# Fan_Feedback.net
KiCad netlist of a schematic drawn in Altium Designer
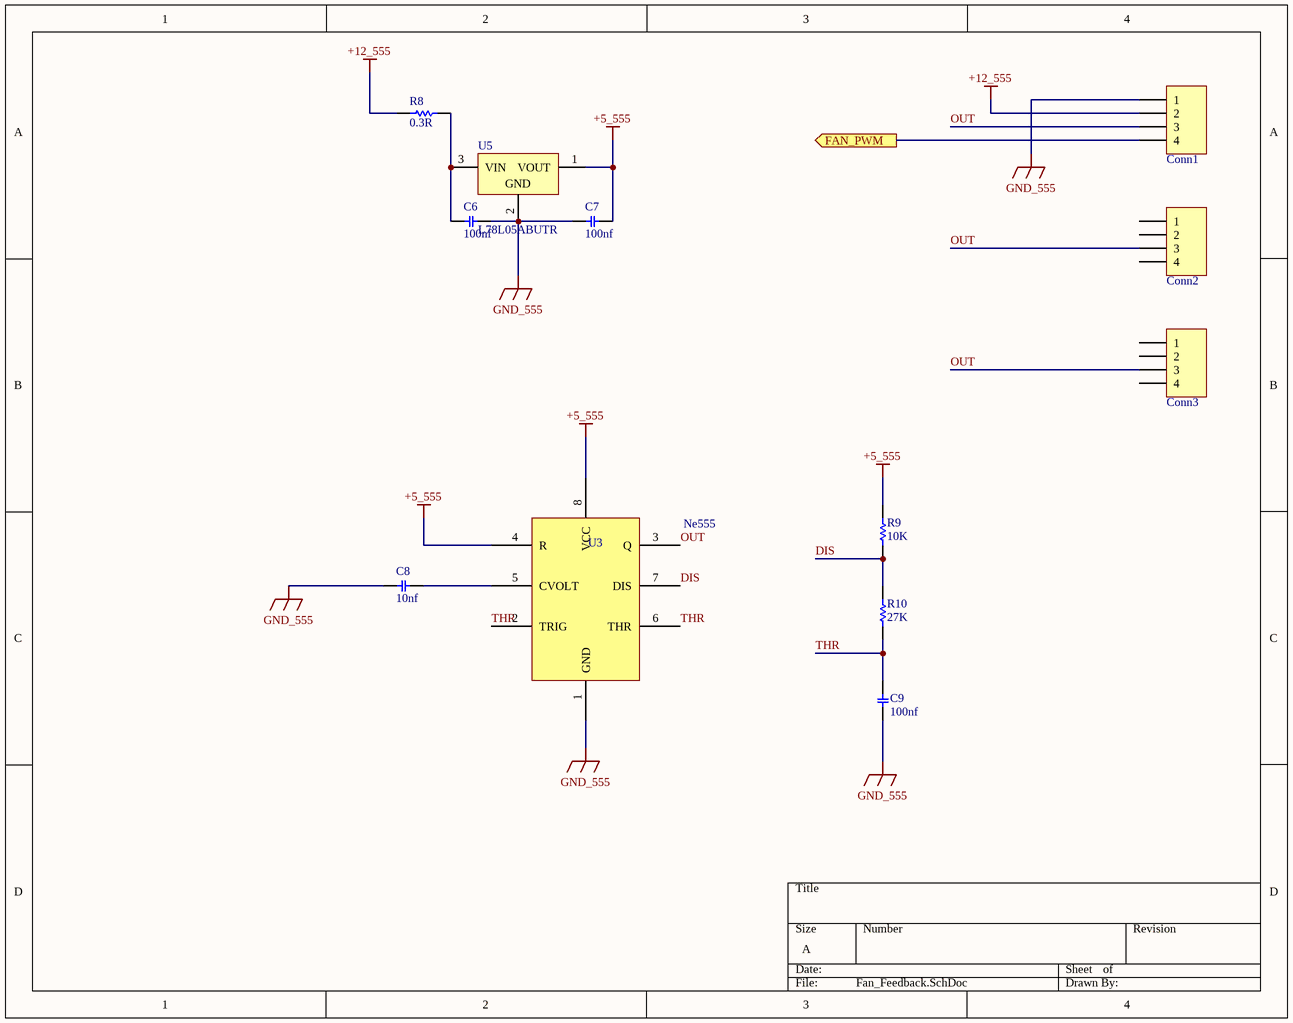
[diagram p0: Fan_Feedback.SchDoc]

(export (version "E")
  (design (tool "Eeschema 10.0.6"))
  (components
    (comp (ref "C6")
      (value "100nf")
      (footprint "C1206")
      (description "Capacitor C SMD 1206")
      (libsource (lib "Capacitor") (part "Capacitor C SMD 1206"))
    )
    (comp (ref "C7")
      (value "100nf")
      (footprint "C1206")
      (description "Capacitor C SMD 1206")
      (libsource (lib "Capacitor") (part "Capacitor C SMD 1206"))
    )
    (comp (ref "C8")
      (value "10nf")
      (footprint "C1206")
      (description "Capacitor C SMD 1206")
      (libsource (lib "Capacitor") (part "Capacitor C SMD 1206"))
    )
    (comp (ref "C9")
      (value "100nf")
      (footprint "C1206")
      (description "Capacitor C SMD 1206")
      (libsource (lib "Capacitor") (part "Capacitor C SMD 1206"))
    )
    (comp (ref "Conn1")
      (value "Telecommunications_4pin")
      (footprint "Teleconn_4pin")
      (description "Telecommunications")
      (libsource (lib "Connector") (part "Telecommunications_4pin"))
    )
    (comp (ref "Conn2")
      (value "Telecommunications_4pin")
      (footprint "Teleconn_4pin")
      (description "Telecommunications")
      (libsource (lib "Connector") (part "Telecommunications_4pin"))
    )
    (comp (ref "Conn3")
      (value "Telecommunications_4pin")
      (footprint "Teleconn_4pin")
      (description "Telecommunications")
      (libsource (lib "Connector") (part "Telecommunications_4pin"))
    )
    (comp (ref "R8")
      (value "0.3R")
      (footprint "SMD-1206-RES")
      (description "Resistor SMD 1206")
      (libsource (lib "Resistor") (part "Resistor SMD 1206"))
    )
    (comp (ref "R9")
      (value "10K")
      (footprint "SMD-1206-RES")
      (description "Resistor SMD 1206")
      (libsource (lib "Resistor") (part "Resistor SMD 1206"))
    )
    (comp (ref "R10")
      (value "27K")
      (footprint "SMD-1206-RES")
      (description "Resistor SMD 1206")
      (libsource (lib "Resistor") (part "Resistor SMD 1206"))
    )
    (comp (ref "U3")
      (value "Ne555")
      (footprint "NE555 SMD")
      (fields (field (name "Comment") "NE555"))
      (libsource (lib "IC") (part "NE555 2"))
    )
    (comp (ref "U5")
      (value "L78L05ABUTR")
      (footprint "SOT-89_N")
      (description "Positive Voltage Regulator, 5V, 4-Pin SOT-89, Tape and Reel")
      (libsource (lib "Altium Content Vault") (part "PM-REG-7805-SIL3"))
    )
  )
  (nets
    (net (code "1") (name "+5_555") (class "Default")
      (node (ref "C7") (pin "2") (pinfunction "2_2") (pintype "passive"))
      (node (ref "R9") (pin "2") (pinfunction "2_2") (pintype "passive"))
      (node (ref "U3") (pin "4") (pinfunction "R_4") (pintype "passive"))
      (node (ref "U3") (pin "8") (pinfunction "VCC_8") (pintype "passive"))
      (node (ref "U5") (pin "1") (pinfunction "VOUT_1") (pintype "power_in"))
    )
    (net (code "2") (name "+12_555") (class "Default")
      (node (ref "Conn1") (pin "2") (pinfunction "2_2") (pintype "passive"))
      (node (ref "R8") (pin "1") (pinfunction "1_1") (pintype "passive"))
    )
    (net (code "3") (name "/DIS") (class "Default")
      (node (ref "R10") (pin "2") (pinfunction "2_2") (pintype "passive"))
      (node (ref "R9") (pin "1") (pinfunction "1_1") (pintype "passive"))
      (node (ref "U3") (pin "7") (pinfunction "DIS_7") (pintype "passive"))
    )
    (net (code "4") (name "/FAN_PWM") (class "Default")
      (node (ref "Conn1") (pin "4") (pinfunction "4_4") (pintype "passive"))
    )
    (net (code "5") (name "/OUT") (class "Default")
      (node (ref "Conn1") (pin "3") (pinfunction "3_3") (pintype "passive"))
      (node (ref "Conn2") (pin "3") (pinfunction "3_3") (pintype "passive"))
      (node (ref "Conn3") (pin "3") (pinfunction "3_3") (pintype "passive"))
      (node (ref "U3") (pin "3") (pinfunction "Q_3") (pintype "passive"))
    )
    (net (code "6") (name "/THR") (class "Default")
      (node (ref "C9") (pin "2") (pinfunction "2_2") (pintype "passive"))
      (node (ref "R10") (pin "1") (pinfunction "1_1") (pintype "passive"))
      (node (ref "U3") (pin "2") (pinfunction "TRIG_2") (pintype "passive"))
      (node (ref "U3") (pin "6") (pinfunction "THR_6") (pintype "passive"))
    )
    (net (code "7") (name "GND_555") (class "Default")
      (node (ref "C6") (pin "2") (pinfunction "2_2") (pintype "passive"))
      (node (ref "C7") (pin "1") (pinfunction "1_1") (pintype "passive"))
      (node (ref "C8") (pin "1") (pinfunction "1_1") (pintype "passive"))
      (node (ref "C9") (pin "1") (pinfunction "1_1") (pintype "passive"))
      (node (ref "Conn1") (pin "1") (pinfunction "1_1") (pintype "passive"))
      (node (ref "U3") (pin "1") (pinfunction "GND_1") (pintype "passive"))
      (node (ref "U5") (pin "2") (pinfunction "GND_2") (pintype "power_in"))
    )
    (net (code "8") (name "Net-(U3-CVOLT)") (class "Default")
      (node (ref "C8") (pin "2") (pinfunction "2_2") (pintype "passive"))
      (node (ref "U3") (pin "5") (pinfunction "CVOLT_5") (pintype "passive"))
    )
    (net (code "9") (name "Net-(U5-VIN)") (class "Default")
      (node (ref "C6") (pin "1") (pinfunction "1_1") (pintype "passive"))
      (node (ref "R8") (pin "2") (pinfunction "2_2") (pintype "passive"))
      (node (ref "U5") (pin "3") (pinfunction "VIN_3") (pintype "power_in"))
    )
    (net (code "10") (name "unconnected-(Conn2-Pad1)") (class "Default")
      (node (ref "Conn2") (pin "1") (pinfunction "1_1") (pintype "passive"))
    )
    (net (code "11") (name "unconnected-(Conn2-Pad2)") (class "Default")
      (node (ref "Conn2") (pin "2") (pinfunction "2_2") (pintype "passive"))
    )
    (net (code "12") (name "unconnected-(Conn2-Pad4)") (class "Default")
      (node (ref "Conn2") (pin "4") (pinfunction "4_4") (pintype "passive"))
    )
    (net (code "13") (name "unconnected-(Conn3-Pad1)") (class "Default")
      (node (ref "Conn3") (pin "1") (pinfunction "1_1") (pintype "passive"))
    )
    (net (code "14") (name "unconnected-(Conn3-Pad2)") (class "Default")
      (node (ref "Conn3") (pin "2") (pinfunction "2_2") (pintype "passive"))
    )
    (net (code "15") (name "unconnected-(Conn3-Pad4)") (class "Default")
      (node (ref "Conn3") (pin "4") (pinfunction "4_4") (pintype "passive"))
    )
  )
)
